# Processor.net
KiCad netlist of a schematic drawn in Altium Designer
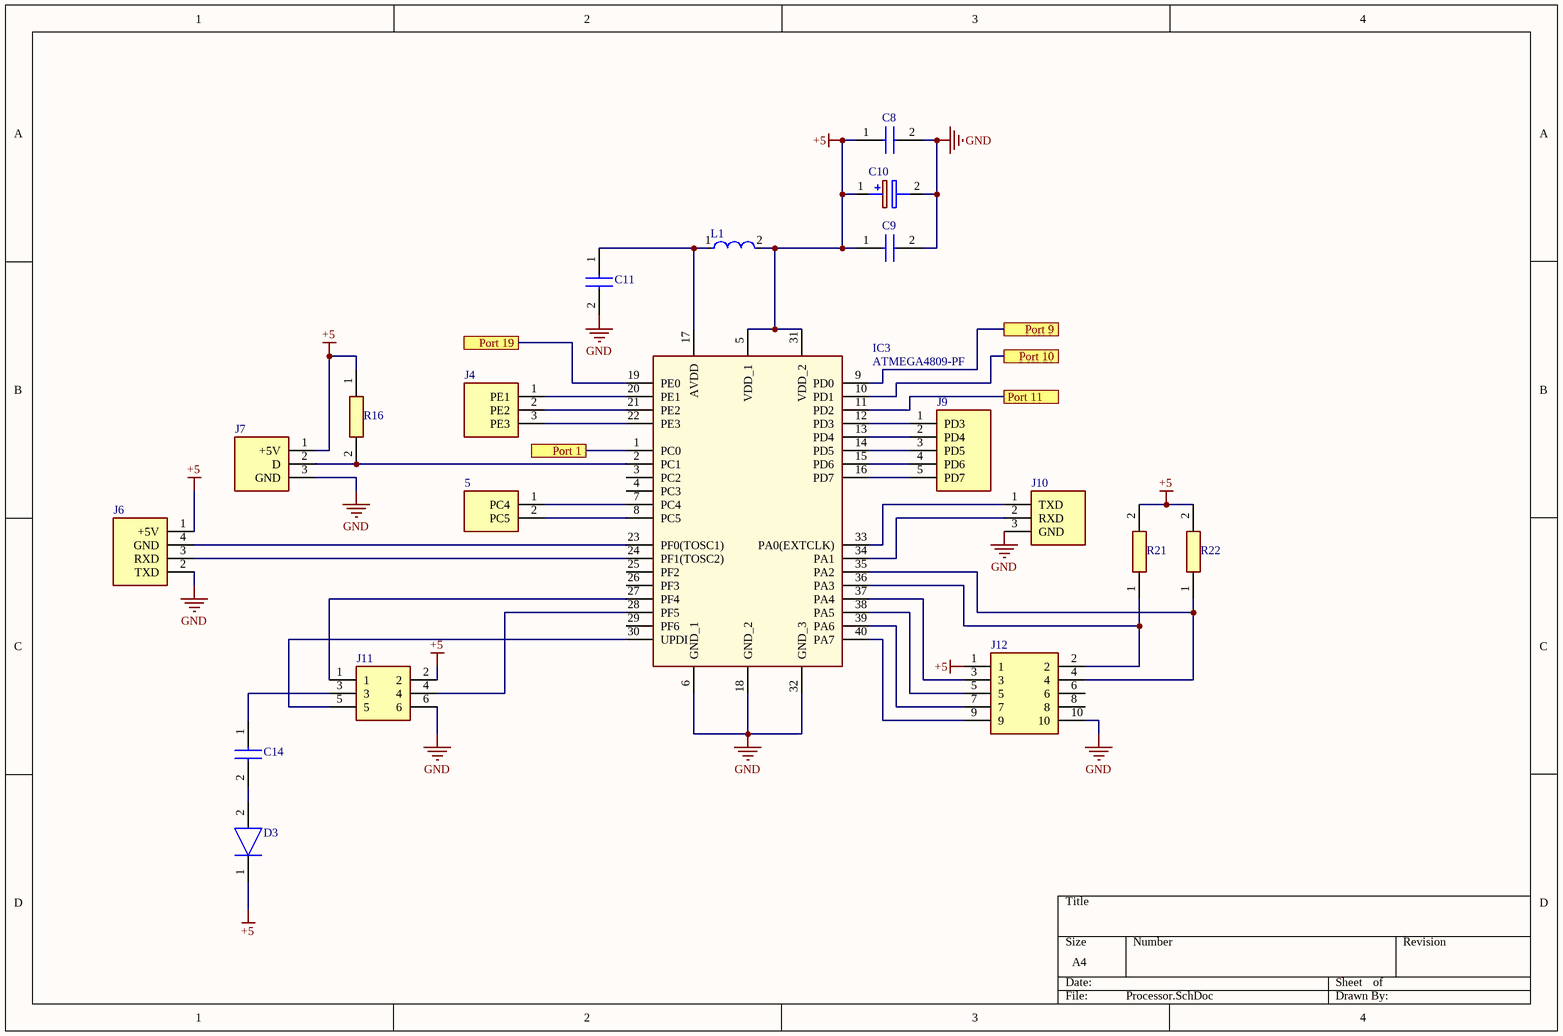
[diagram p0: Processor.SchDoc]

(export (version "E")
  (design (tool "Eeschema 10.0.6"))
  (components
    (comp (ref "5")
      (value "1711725")
      (footprint "1711725")
      (description "Connector")
      (libsource (lib "Schlib1") (part "1711725"))
    )
    (comp (ref "C8")
      (value "C0805C104K5RAC7411")
      (footprint "100nF")
      (description "Capacitor  0.1 uF 50VDC")
      (fields (field (name "MOUSER2 PART NUMBER") "80-C0805C104K5RACLR"))
      (libsource (lib "Schlib1") (part "C0805C104K5RAC7411"))
    )
    (comp (ref "C9")
      (value "C0805C104K5RAC7411")
      (footprint "100nF")
      (description "Capacitor  0.1 uF 50VDC")
      (fields (field (name "MOUSER2 PART NUMBER") "80-C0805C104K5RACLR"))
      (libsource (lib "Schlib1") (part "C0805C104K5RAC7411"))
    )
    (comp (ref "C10")
      (value "EEU-FR1H100")
      (footprint "10µF 50V")
      (description "Capacitor Polarised 50VDC 10uF")
      (fields (field (name "MOUSER2 PART NUMBER") "667-EEU-FR1H100"))
      (libsource (lib "Schlib1") (part "EEU-FR1H100"))
    )
    (comp (ref "C11")
      (value "C0805C104K5RAC7411")
      (footprint "100nF")
      (description "Capacitor  0.1 uF 50VDC")
      (fields (field (name "MOUSER2 PART NUMBER") "80-C0805C104K5RACLR"))
      (libsource (lib "Schlib1") (part "C0805C104K5RAC7411"))
    )
    (comp (ref "C14")
      (value "C0805C104K5RAC7411")
      (footprint "100nF")
      (description "Capacitor  0.1 uF 50VDC")
      (fields (field (name "MOUSER2 PART NUMBER") "80-C0805C104K5RACLR"))
      (libsource (lib "Schlib1") (part "C0805C104K5RAC7411"))
    )
    (comp (ref "D3")
      (value "1N4148WS_R1_00001")
      (footprint "SODFL2512X95N")
      (description "Diode")
      (libsource (lib "Schlib1") (part "1N4148WS_R1_00001"))
    )
    (comp (ref "IC3")
      (value "ATMEGA4809-PF")
      (footprint "DIP1543W58P254L5175H635Q40N")
      (description "Integrated Circuit")
      (fields (field (name "MOUSER2 PART NUMBER") "556-ATMEGA4809-PF"))
      (libsource (lib "Schlib1") (part "ATMEGA4809-PF"))
    )
    (comp (ref "J4")
      (value "10129378-903001BLF")
      (footprint "HDRV3W67P0X254_1X3_762X241X858P")
      (description "Connector")
      (libsource (lib "") (part "10129378-903001BLF_1"))
    )
    (comp (ref "J6")
      (value "10129378-904001BLF")
      (footprint "HDRV4W67P0X254_1X4_1270X241X858P")
      (description "Connector")
      (libsource (lib "Schlib1") (part "10129378-904001BLF"))
    )
    (comp (ref "J7")
      (value "10129378-903001BLF")
      (footprint "HDRV3W67P0X254_1X3_762X241X858P")
      (description "Connector")
      (libsource (lib "") (part "10129378-903001BLF_1"))
    )
    (comp (ref "J9")
      (value "10129378-905001BLF")
      (footprint "HDRV5W67P0X254_1X5_1270X241X858P")
      (description "Connector")
      (libsource (lib "Schlib1") (part "10129378-905001BLF"))
    )
    (comp (ref "J10")
      (value "10129378-903001BLF")
      (footprint "HDRV3W67P0X254_1X3_762X241X858P")
      (description "Connector")
      (libsource (lib "Schlib1") (part "10129378-903001BLF"))
    )
    (comp (ref "J11")
      (value "10129381-906002BLF")
      (footprint "HDRV6W67P254_2X3_762X483X858P")
      (description "Connector")
      (fields (field (name "MOUSER2 PART NUMBER") "649-1012938190602BLF"))
      (libsource (lib "Schlib1") (part "10129381-906002BLF"))
    )
    (comp (ref "J12")
      (value "N2510-6002RB")
      (footprint "1PinBox")
      (description "Connector")
      (fields (field (name "MOUSER2 PART NUMBER") "517-N2510-6002RB"))
      (libsource (lib "Schlib1") (part "N2510-6002RB"))
    )
    (comp (ref "L1")
      (value "CBC3225T100MR")
      (footprint "FP-CB3225-IPC_A")
      (description "SMD Inductors 10uH ±20% 0.9A 0.1729Ω 1210")
      (fields (field (name "TOLERANCE") "20%"))
      (libsource (lib "Altium Content Vault") (part "725321dda6339637d4d059423bc1c3c"))
    )
    (comp (ref "R16")
      (value "CRCW08054K70FKEAHP")
      (footprint "RESC2012X50N")
      (description "Resistor 4.7KOhm")
      (fields (field (name "MOUSER2 PART NUMBER") "71-CRCW08054K70FKEAH"))
      (libsource (lib "") (part "CRCW08054K70FKEAHP_1"))
    )
    (comp (ref "R21")
      (value "CRCW08054K70FKEAHP")
      (footprint "RESC2012X50N")
      (description "Resistor 4.7KOhm")
      (fields (field (name "MOUSER2 PART NUMBER") "71-CRCW08054K70FKEAH"))
      (libsource (lib "Schlib1") (part "CRCW08054K70FKEAHP"))
    )
    (comp (ref "R22")
      (value "CRCW08054K70FKEAHP")
      (footprint "RESC2012X50N")
      (description "Resistor 4.7KOhm")
      (fields (field (name "MOUSER2 PART NUMBER") "71-CRCW08054K70FKEAH"))
      (libsource (lib "Schlib1") (part "CRCW08054K70FKEAHP"))
    )
  )
  (nets
    (net (code "1") (name "+5") (class "Default")
      (node (ref "C10") (pin "1") (pinfunction "+_1") (pintype "power_in"))
      (node (ref "C8") (pin "1") (pinfunction "1_1") (pintype "passive"))
      (node (ref "C9") (pin "1") (pinfunction "1_1") (pintype "passive"))
      (node (ref "D3") (pin "1") (pinfunction "K_1") (pintype "passive"))
      (node (ref "IC3") (pin "31") (pinfunction "VDD_2_31") (pintype "passive"))
      (node (ref "IC3") (pin "5") (pinfunction "VDD_1_5") (pintype "passive"))
      (node (ref "J11") (pin "2") (pinfunction "2_2") (pintype "passive"))
      (node (ref "J12") (pin "1") (pinfunction "1_1") (pintype "passive"))
      (node (ref "J6") (pin "1") (pinfunction "+5V_1") (pintype "passive"))
      (node (ref "J7") (pin "1") (pinfunction "+5V_1") (pintype "passive"))
      (node (ref "L1") (pin "2") (pinfunction "2_2") (pintype "passive"))
      (node (ref "R16") (pin "1") (pinfunction "1_1") (pintype "passive"))
      (node (ref "R21") (pin "2") (pinfunction "2_2") (pintype "passive"))
      (node (ref "R22") (pin "2") (pinfunction "2_2") (pintype "passive"))
    )
    (net (code "2") (name "/Port 1") (class "Default")
      (node (ref "IC3") (pin "1") (pinfunction "PC0_1") (pintype "passive"))
    )
    (net (code "3") (name "/Port 9") (class "Default")
      (node (ref "IC3") (pin "9") (pinfunction "PD0_9") (pintype "passive"))
    )
    (net (code "4") (name "/Port 10") (class "Default")
      (node (ref "IC3") (pin "10") (pinfunction "PD1_10") (pintype "passive"))
    )
    (net (code "5") (name "/Port 11") (class "Default")
      (node (ref "IC3") (pin "11") (pinfunction "PD2_11") (pintype "passive"))
    )
    (net (code "6") (name "/Port 19") (class "Default")
      (node (ref "IC3") (pin "19") (pinfunction "PE0_19") (pintype "passive"))
    )
    (net (code "7") (name "GND") (class "Default")
      (node (ref "C10") (pin "2") (pinfunction "-_2") (pintype "power_in"))
      (node (ref "C11") (pin "2") (pinfunction "2_2") (pintype "passive"))
      (node (ref "C8") (pin "2") (pinfunction "2_2") (pintype "passive"))
      (node (ref "C9") (pin "2") (pinfunction "2_2") (pintype "passive"))
      (node (ref "IC3") (pin "18") (pinfunction "GND_2_18") (pintype "passive"))
      (node (ref "IC3") (pin "32") (pinfunction "GND_3_32") (pintype "passive"))
      (node (ref "IC3") (pin "6") (pinfunction "GND_1_6") (pintype "passive"))
      (node (ref "J10") (pin "3") (pinfunction "GND_3") (pintype "passive"))
      (node (ref "J11") (pin "6") (pinfunction "6_6") (pintype "passive"))
      (node (ref "J12") (pin "10") (pinfunction "10_10") (pintype "passive"))
      (node (ref "J6") (pin "2") (pinfunction "TXD_2") (pintype "passive"))
      (node (ref "J7") (pin "3") (pinfunction "GND_3") (pintype "passive"))
    )
    (net (code "8") (name "Net-(5-PC4)") (class "Default")
      (node (ref "5") (pin "1") (pinfunction "PC4_1") (pintype "passive"))
      (node (ref "IC3") (pin "7") (pinfunction "PC4_7") (pintype "passive"))
    )
    (net (code "9") (name "Net-(5-PC5)") (class "Default")
      (node (ref "5") (pin "2") (pinfunction "PC5_2") (pintype "passive"))
      (node (ref "IC3") (pin "8") (pinfunction "PC5_8") (pintype "passive"))
    )
    (net (code "10") (name "Net-(C14-Pad1)") (class "Default")
      (node (ref "C14") (pin "1") (pinfunction "1_1") (pintype "passive"))
      (node (ref "J11") (pin "3") (pinfunction "3_3") (pintype "passive"))
    )
    (net (code "11") (name "Net-(D3-A)") (class "Default")
      (node (ref "C14") (pin "2") (pinfunction "2_2") (pintype "passive"))
      (node (ref "D3") (pin "2") (pinfunction "A_2") (pintype "passive"))
    )
    (net (code "12") (name "Net-(IC3-AVDD)") (class "Default")
      (node (ref "C11") (pin "1") (pinfunction "1_1") (pintype "passive"))
      (node (ref "IC3") (pin "17") (pinfunction "AVDD_17") (pintype "passive"))
      (node (ref "L1") (pin "1") (pinfunction "1_1") (pintype "passive"))
    )
    (net (code "13") (name "Net-(IC3-PA0(EXTCLK))") (class "Default")
      (node (ref "IC3") (pin "33") (pinfunction "PA0(EXTCLK)_33") (pintype "passive"))
      (node (ref "J10") (pin "1") (pinfunction "TXD_1") (pintype "passive"))
    )
    (net (code "14") (name "Net-(IC3-PA1)") (class "Default")
      (node (ref "IC3") (pin "34") (pinfunction "PA1_34") (pintype "passive"))
      (node (ref "J10") (pin "2") (pinfunction "RXD_2") (pintype "passive"))
    )
    (net (code "15") (name "Net-(IC3-PA2)") (class "Default")
      (node (ref "IC3") (pin "35") (pinfunction "PA2_35") (pintype "passive"))
      (node (ref "J12") (pin "4") (pinfunction "4_4") (pintype "passive"))
      (node (ref "R22") (pin "1") (pinfunction "1_1") (pintype "passive"))
    )
    (net (code "16") (name "Net-(IC3-PA3)") (class "Default")
      (node (ref "IC3") (pin "36") (pinfunction "PA3_36") (pintype "passive"))
      (node (ref "J12") (pin "2") (pinfunction "2_2") (pintype "passive"))
      (node (ref "R21") (pin "1") (pinfunction "1_1") (pintype "passive"))
    )
    (net (code "17") (name "Net-(IC3-PA4)") (class "Default")
      (node (ref "IC3") (pin "37") (pinfunction "PA4_37") (pintype "passive"))
      (node (ref "J12") (pin "3") (pinfunction "3_3") (pintype "passive"))
    )
    (net (code "18") (name "Net-(IC3-PA5)") (class "Default")
      (node (ref "IC3") (pin "38") (pinfunction "PA5_38") (pintype "passive"))
      (node (ref "J12") (pin "5") (pinfunction "5_5") (pintype "passive"))
    )
    (net (code "19") (name "Net-(IC3-PA6)") (class "Default")
      (node (ref "IC3") (pin "39") (pinfunction "PA6_39") (pintype "passive"))
      (node (ref "J12") (pin "7") (pinfunction "7_7") (pintype "passive"))
    )
    (net (code "20") (name "Net-(IC3-PA7)") (class "Default")
      (node (ref "IC3") (pin "40") (pinfunction "PA7_40") (pintype "passive"))
      (node (ref "J12") (pin "9") (pinfunction "9_9") (pintype "passive"))
    )
    (net (code "21") (name "Net-(IC3-PC1)") (class "Default")
      (node (ref "IC3") (pin "2") (pinfunction "PC1_2") (pintype "passive"))
      (node (ref "J7") (pin "2") (pinfunction "D_2") (pintype "passive"))
      (node (ref "R16") (pin "2") (pinfunction "2_2") (pintype "passive"))
    )
    (net (code "22") (name "Net-(IC3-PD3)") (class "Default")
      (node (ref "IC3") (pin "12") (pinfunction "PD3_12") (pintype "passive"))
      (node (ref "J9") (pin "1") (pinfunction "PD3_1") (pintype "passive"))
    )
    (net (code "23") (name "Net-(IC3-PD4)") (class "Default")
      (node (ref "IC3") (pin "13") (pinfunction "PD4_13") (pintype "passive"))
      (node (ref "J9") (pin "2") (pinfunction "PD4_2") (pintype "passive"))
    )
    (net (code "24") (name "Net-(IC3-PD5)") (class "Default")
      (node (ref "IC3") (pin "14") (pinfunction "PD5_14") (pintype "passive"))
      (node (ref "J9") (pin "3") (pinfunction "PD5_3") (pintype "passive"))
    )
    (net (code "25") (name "Net-(IC3-PD6)") (class "Default")
      (node (ref "IC3") (pin "15") (pinfunction "PD6_15") (pintype "passive"))
      (node (ref "J9") (pin "4") (pinfunction "PD6_4") (pintype "passive"))
    )
    (net (code "26") (name "Net-(IC3-PD7)") (class "Default")
      (node (ref "IC3") (pin "16") (pinfunction "PD7_16") (pintype "passive"))
      (node (ref "J9") (pin "5") (pinfunction "PD7_5") (pintype "passive"))
    )
    (net (code "27") (name "Net-(IC3-PE1)") (class "Default")
      (node (ref "IC3") (pin "20") (pinfunction "PE1_20") (pintype "passive"))
      (node (ref "J4") (pin "1") (pinfunction "+5V_1") (pintype "passive"))
    )
    (net (code "28") (name "Net-(IC3-PE2)") (class "Default")
      (node (ref "IC3") (pin "21") (pinfunction "PE2_21") (pintype "passive"))
      (node (ref "J4") (pin "2") (pinfunction "D_2") (pintype "passive"))
    )
    (net (code "29") (name "Net-(IC3-PE3)") (class "Default")
      (node (ref "IC3") (pin "22") (pinfunction "PE3_22") (pintype "passive"))
      (node (ref "J4") (pin "3") (pinfunction "GND_3") (pintype "passive"))
    )
    (net (code "30") (name "Net-(IC3-PF0(TOSC1))") (class "Default")
      (node (ref "IC3") (pin "23") (pinfunction "PF0(TOSC1)_23") (pintype "passive"))
      (node (ref "J6") (pin "4") (pinfunction "GND_4") (pintype "passive"))
    )
    (net (code "31") (name "Net-(IC3-PF1(TOSC2))") (class "Default")
      (node (ref "IC3") (pin "24") (pinfunction "PF1(TOSC2)_24") (pintype "passive"))
      (node (ref "J6") (pin "3") (pinfunction "RXD_3") (pintype "passive"))
    )
    (net (code "32") (name "Net-(IC3-PF4)") (class "Default")
      (node (ref "IC3") (pin "27") (pinfunction "PF4_27") (pintype "passive"))
      (node (ref "J11") (pin "1") (pinfunction "1_1") (pintype "passive"))
    )
    (net (code "33") (name "Net-(IC3-PF5)") (class "Default")
      (node (ref "IC3") (pin "28") (pinfunction "PF5_28") (pintype "passive"))
      (node (ref "J11") (pin "4") (pinfunction "4_4") (pintype "passive"))
    )
    (net (code "34") (name "Net-(IC3-UPDI)") (class "Default")
      (node (ref "IC3") (pin "30") (pinfunction "UPDI_30") (pintype "passive"))
      (node (ref "J11") (pin "5") (pinfunction "5_5") (pintype "passive"))
    )
    (net (code "35") (name "unconnected-(IC3-PC2-Pad3)") (class "Default")
      (node (ref "IC3") (pin "3") (pinfunction "PC2_3") (pintype "passive"))
    )
    (net (code "36") (name "unconnected-(IC3-PC3-Pad4)") (class "Default")
      (node (ref "IC3") (pin "4") (pinfunction "PC3_4") (pintype "passive"))
    )
    (net (code "37") (name "unconnected-(IC3-PF2-Pad25)") (class "Default")
      (node (ref "IC3") (pin "25") (pinfunction "PF2_25") (pintype "passive"))
    )
    (net (code "38") (name "unconnected-(IC3-PF3-Pad26)") (class "Default")
      (node (ref "IC3") (pin "26") (pinfunction "PF3_26") (pintype "passive"))
    )
    (net (code "39") (name "unconnected-(IC3-PF6-Pad29)") (class "Default")
      (node (ref "IC3") (pin "29") (pinfunction "PF6_29") (pintype "passive"))
    )
    (net (code "40") (name "unconnected-(J12-Pad6)") (class "Default")
      (node (ref "J12") (pin "6") (pinfunction "6_6") (pintype "passive"))
    )
    (net (code "41") (name "unconnected-(J12-Pad8)") (class "Default")
      (node (ref "J12") (pin "8") (pinfunction "8_8") (pintype "passive"))
    )
  )
)
